# Power.net
KiCad netlist of a schematic drawn in EAGLE
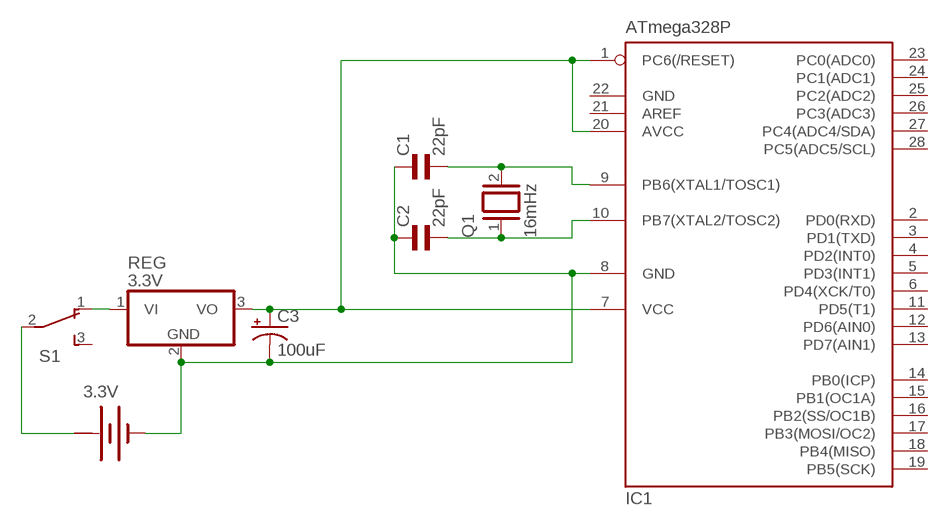
[diagram p0: schematic, sheet 1]

(export (version "E")
  (design (tool "Eeschema 10.0.6"))
  (components
    (comp (ref "3.3V")
      (value "BATTERY")
      (footprint "eagle-import:BATTERY")
      (libsource (lib "eagle-import") (part "BATTERY"))
    )
    (comp (ref "C1")
      (value "22pF")
      (footprint "eagle-import:EU25-10")
      (libsource (lib "eagle-import") (part "EL-BI25-10AXIAL"))
    )
    (comp (ref "C2")
      (value "22pF")
      (footprint "eagle-import:EU25-10")
      (libsource (lib "eagle-import") (part "EL-BI25-10AXIAL"))
    )
    (comp (ref "C3")
      (value "100uF")
      (footprint "eagle-import:085CS_1AR")
      (libsource (lib "eagle-import") (part "CPOL-US085CS-1AR"))
    )
    (comp (ref "IC1")
      (value "ATmega328P")
      (footprint "eagle-import:DIL28-3")
      (libsource (lib "eagle-import") (part "MEGA8-P"))
    )
    (comp (ref "Q1")
      (value "16mHz")
      (footprint "eagle-import:Q")
      (libsource (lib "eagle-import") (part "XTAL"))
    )
    (comp (ref "REG")
      (value "3.3V")
      (footprint "eagle-import:TO220H")
      (libsource (lib "eagle-import") (part "LM340?-H05"))
    )
    (comp (ref "S1")
      (value "TL36PO")
      (footprint "eagle-import:TL3XPO")
      (libsource (lib "eagle-import") (part "TL36PO"))
    )
  )
  (nets
    (net (code "1") (name "/+") (class "Default")
      (node (ref "3.3V") (pin "+@1") (pinfunction "+_+@1") (pintype "power_in"))
    )
    (net (code "2") (name "/GND") (class "Default")
      (node (ref "IC1") (pin "22") (pinfunction "GND_22") (pintype "power_in"))
    )
    (net (code "3") (name "Net-(IC1-AVCC)") (class "Default")
      (node (ref "C3") (pin "+") (pinfunction "+_+") (pintype "passive"))
      (node (ref "IC1") (pin "1") (pinfunction "PC6(/RESET)_1") (pintype "bidirectional"))
      (node (ref "IC1") (pin "20") (pinfunction "AVCC_20") (pintype "power_in"))
      (node (ref "IC1") (pin "7") (pinfunction "VCC_7") (pintype "power_in"))
      (node (ref "REG") (pin "3") (pinfunction "VO_3") (pintype "passive"))
    )
    (net (code "4") (name "Net-(IC1-PB6(XTAL1{slash}TOSC1))") (class "Default")
      (node (ref "C1") (pin "2") (pinfunction "2_2") (pintype "passive"))
      (node (ref "IC1") (pin "9") (pinfunction "PB6(XTAL1/TOSC1)_9") (pintype "bidirectional"))
      (node (ref "Q1") (pin "2") (pinfunction "2_2") (pintype "passive"))
    )
    (net (code "5") (name "Net-(IC1-PB7(XTAL2{slash}TOSC2))") (class "Default")
      (node (ref "C2") (pin "2") (pinfunction "2_2") (pintype "passive"))
      (node (ref "IC1") (pin "10") (pinfunction "PB7(XTAL2/TOSC2)_10") (pintype "bidirectional"))
      (node (ref "Q1") (pin "1") (pinfunction "1_1") (pintype "passive"))
    )
    (net (code "6") (name "Net-(REG-GND)") (class "Default")
      (node (ref "3.3V") (pin "-") (pinfunction "-_-") (pintype "power_in"))
      (node (ref "C1") (pin "1") (pinfunction "1_1") (pintype "passive"))
      (node (ref "C2") (pin "1") (pinfunction "1_1") (pintype "passive"))
      (node (ref "C3") (pin "-") (pinfunction "-_-") (pintype "passive"))
      (node (ref "IC1") (pin "8") (pinfunction "GND_8") (pintype "power_in"))
      (node (ref "REG") (pin "2") (pinfunction "GND_2") (pintype "passive"))
    )
    (net (code "7") (name "Net-(REG-VI)") (class "Default")
      (node (ref "REG") (pin "1") (pinfunction "VI_1") (pintype "input"))
      (node (ref "S1") (pin "1") (pinfunction "O_1") (pintype "passive"))
    )
    (net (code "8") (name "Net-(S1-P)") (class "Default")
      (node (ref "3.3V") (pin "+") (pinfunction "+_+") (pintype "power_in"))
      (node (ref "S1") (pin "2") (pinfunction "P_2") (pintype "passive"))
    )
    (net (code "9") (name "unconnected-(IC1-AREF-Pad21)") (class "Default")
      (node (ref "IC1") (pin "21") (pinfunction "AREF_21") (pintype "passive"))
    )
    (net (code "10") (name "unconnected-(IC1-PB0(ICP)-Pad14)") (class "Default")
      (node (ref "IC1") (pin "14") (pinfunction "PB0(ICP)_14") (pintype "bidirectional"))
    )
    (net (code "11") (name "unconnected-(IC1-PB1(OC1A)-Pad15)") (class "Default")
      (node (ref "IC1") (pin "15") (pinfunction "PB1(OC1A)_15") (pintype "bidirectional"))
    )
    (net (code "12") (name "unconnected-(IC1-PB2(SS{slash}OC1B)-Pad16)") (class "Default")
      (node (ref "IC1") (pin "16") (pinfunction "PB2(SS/OC1B)_16") (pintype "bidirectional"))
    )
    (net (code "13") (name "unconnected-(IC1-PB3(MOSI{slash}OC2)-Pad17)") (class "Default")
      (node (ref "IC1") (pin "17") (pinfunction "PB3(MOSI/OC2)_17") (pintype "bidirectional"))
    )
    (net (code "14") (name "unconnected-(IC1-PB4(MISO)-Pad18)") (class "Default")
      (node (ref "IC1") (pin "18") (pinfunction "PB4(MISO)_18") (pintype "bidirectional"))
    )
    (net (code "15") (name "unconnected-(IC1-PB5(SCK)-Pad19)") (class "Default")
      (node (ref "IC1") (pin "19") (pinfunction "PB5(SCK)_19") (pintype "bidirectional"))
    )
    (net (code "16") (name "unconnected-(IC1-PC0(ADC0)-Pad23)") (class "Default")
      (node (ref "IC1") (pin "23") (pinfunction "PC0(ADC0)_23") (pintype "bidirectional"))
    )
    (net (code "17") (name "unconnected-(IC1-PC1(ADC1)-Pad24)") (class "Default")
      (node (ref "IC1") (pin "24") (pinfunction "PC1(ADC1)_24") (pintype "bidirectional"))
    )
    (net (code "18") (name "unconnected-(IC1-PC2(ADC2)-Pad25)") (class "Default")
      (node (ref "IC1") (pin "25") (pinfunction "PC2(ADC2)_25") (pintype "bidirectional"))
    )
    (net (code "19") (name "unconnected-(IC1-PC3(ADC3)-Pad26)") (class "Default")
      (node (ref "IC1") (pin "26") (pinfunction "PC3(ADC3)_26") (pintype "bidirectional"))
    )
    (net (code "20") (name "unconnected-(IC1-PC4(ADC4{slash}SDA)-Pad27)") (class "Default")
      (node (ref "IC1") (pin "27") (pinfunction "PC4(ADC4/SDA)_27") (pintype "bidirectional"))
    )
    (net (code "21") (name "unconnected-(IC1-PC5(ADC5{slash}SCL)-Pad28)") (class "Default")
      (node (ref "IC1") (pin "28") (pinfunction "PC5(ADC5/SCL)_28") (pintype "bidirectional"))
    )
    (net (code "22") (name "unconnected-(IC1-PD0(RXD)-Pad2)") (class "Default")
      (node (ref "IC1") (pin "2") (pinfunction "PD0(RXD)_2") (pintype "bidirectional"))
    )
    (net (code "23") (name "unconnected-(IC1-PD1(TXD)-Pad3)") (class "Default")
      (node (ref "IC1") (pin "3") (pinfunction "PD1(TXD)_3") (pintype "bidirectional"))
    )
    (net (code "24") (name "unconnected-(IC1-PD2(INT0)-Pad4)") (class "Default")
      (node (ref "IC1") (pin "4") (pinfunction "PD2(INT0)_4") (pintype "bidirectional"))
    )
    (net (code "25") (name "unconnected-(IC1-PD3(INT1)-Pad5)") (class "Default")
      (node (ref "IC1") (pin "5") (pinfunction "PD3(INT1)_5") (pintype "bidirectional"))
    )
    (net (code "26") (name "unconnected-(IC1-PD4(XCK{slash}T0)-Pad6)") (class "Default")
      (node (ref "IC1") (pin "6") (pinfunction "PD4(XCK/T0)_6") (pintype "bidirectional"))
    )
    (net (code "27") (name "unconnected-(IC1-PD5(T1)-Pad11)") (class "Default")
      (node (ref "IC1") (pin "11") (pinfunction "PD5(T1)_11") (pintype "bidirectional"))
    )
    (net (code "28") (name "unconnected-(IC1-PD6(AIN0)-Pad12)") (class "Default")
      (node (ref "IC1") (pin "12") (pinfunction "PD6(AIN0)_12") (pintype "bidirectional"))
    )
    (net (code "29") (name "unconnected-(IC1-PD7(AIN1)-Pad13)") (class "Default")
      (node (ref "IC1") (pin "13") (pinfunction "PD7(AIN1)_13") (pintype "bidirectional"))
    )
    (net (code "30") (name "unconnected-(S1-S-Pad3)") (class "Default")
      (node (ref "S1") (pin "3") (pinfunction "S_3") (pintype "passive"))
    )
  )
)
